# Modular_BO.net
KiCad netlist of a schematic drawn in Altium Designer
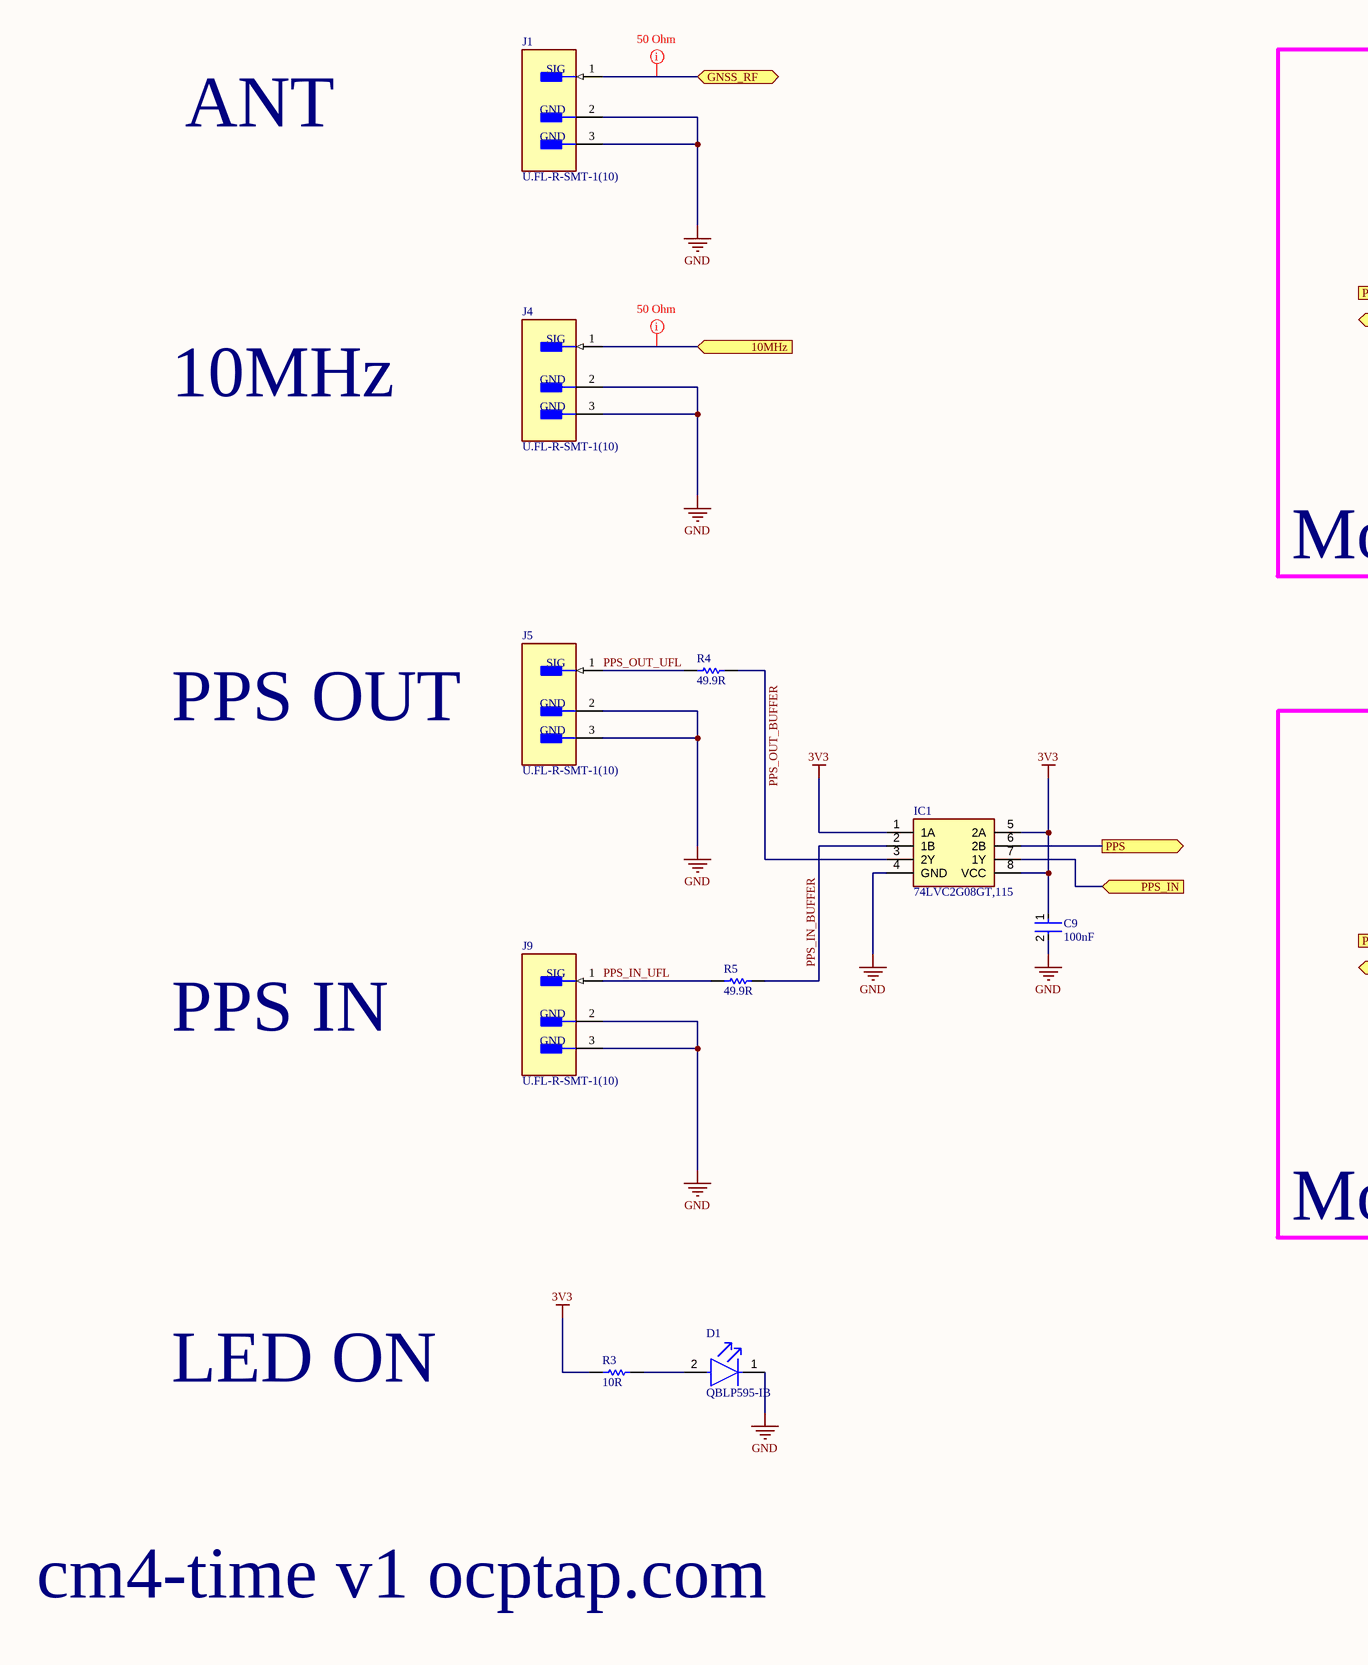
[diagram p0: Modular_BO.SchDoc, left]
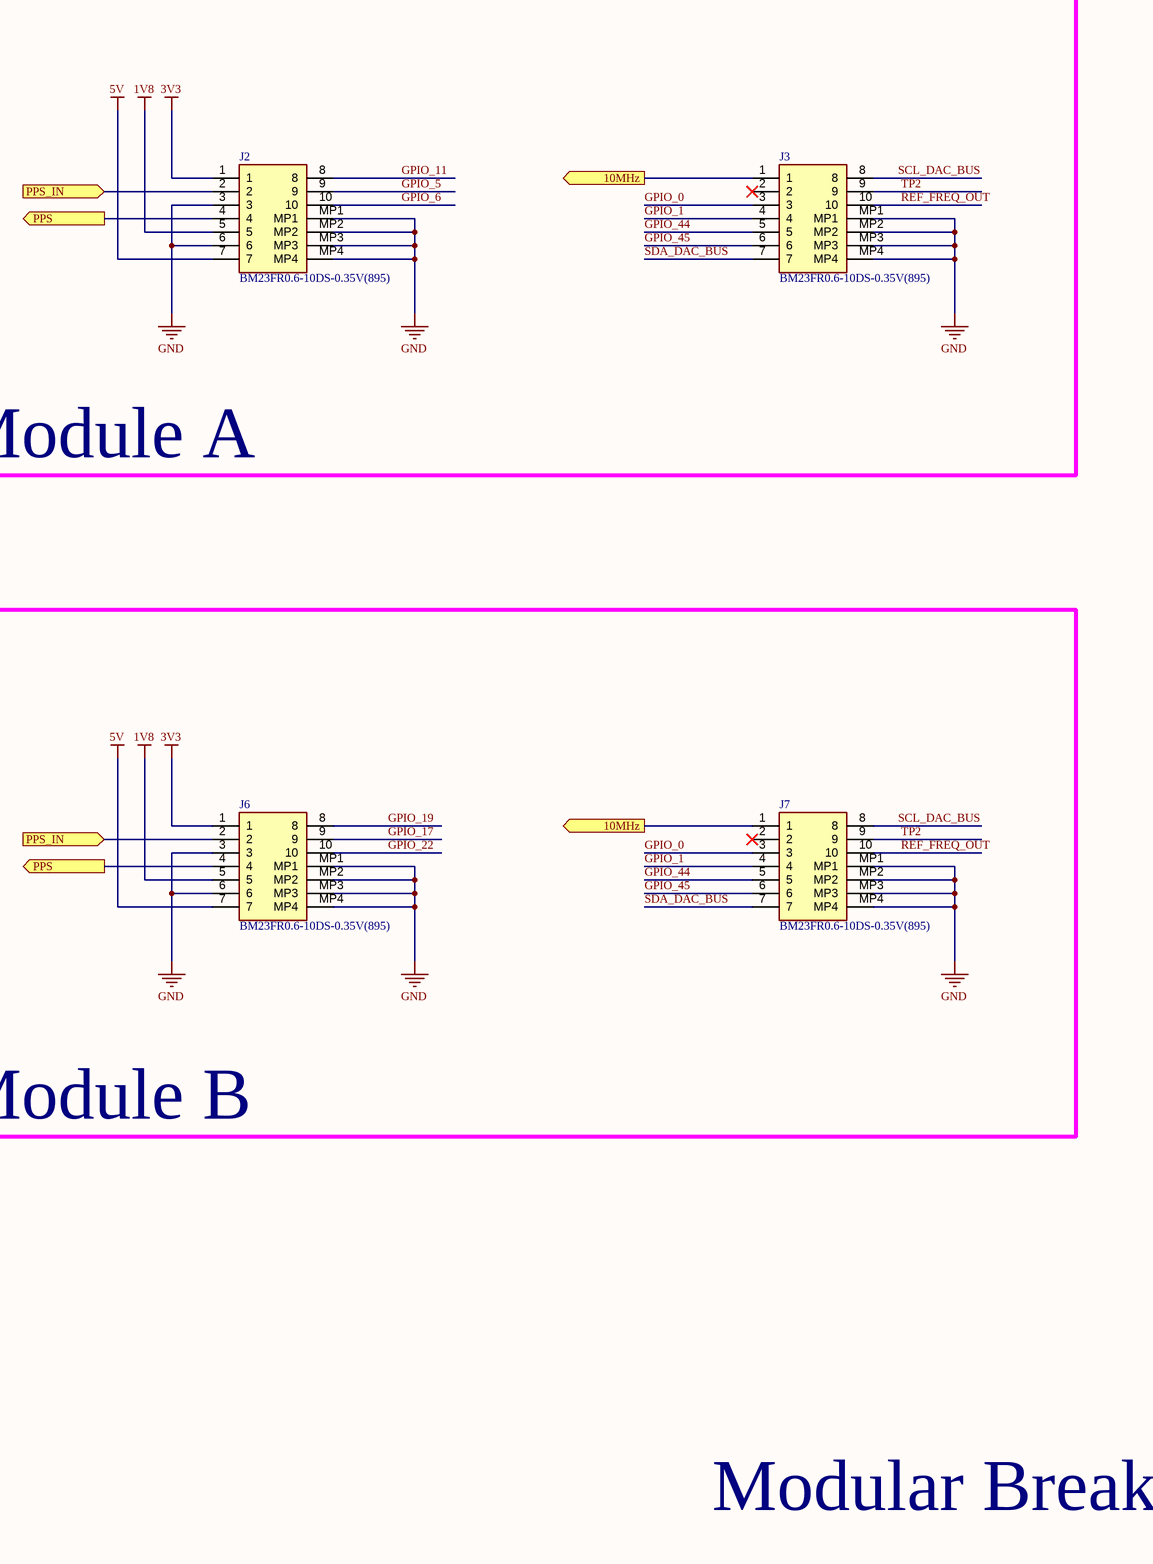
[diagram p1: Modular_BO.SchDoc, right]

(export (version "E")
  (design (tool "Eeschema 10.0.6"))
  (components
    (comp (ref "C9")
      (value "100nF")
      (footprint "FP-C0603C-CF-MFG")
      (description "CAP CER 0.1UF 50V 20% X7R 0603")
      (fields
        (field (name "MANUFACTURER PART NUMBER") "C0603C104M5RACTU")
        (field (name "MANUFACTURER") "KEMET")
      )
      (libsource (lib "Altium Content Vault") (part "b4654b650e69147ec39a6b967a45e02"))
    )
    (comp (ref "D1")
      (value "QBLP595-IB")
      (footprint "FP-QBLP595-IB-MFG")
      (description "LED BLUE CLEAR 0402 SMD")
      (libsource (lib "Altium Content Vault") (part "8706943c75ba83719d021d2fdc84c58"))
    )
    (comp (ref "IC1")
      (value "74LVC2G08GT,115")
      (footprint "SamacSys:74AVC9112GTX")
      (description "Integrated Circuit")
      (fields (field (name "MOUSER PART NUMBER") "771-LVC2G08GT115"))
      (libsource (lib "*") (part "74LVC2G08GT,115"))
    )
    (comp (ref "J1")
      (value "U.FL-R-SMT-1(10)")
      (footprint "FP-U_FL-R-SMT-1_10-MFG")
      (description "CONN U.FL RCPT STR 50 OHM SMD")
      (libsource (lib "Altium Content Vault") (part "7158abf7d987fa84906f6fb0d115710"))
    )
    (comp (ref "J2")
      (value "BM23FR0.6-10DS-0.35V(895)")
      (footprint "SamacSys:BM23FR0810DS035V895")
      (description "Connector")
      (fields
        (field (name "MANUFACTURER_PART_NUMBER") "BM23FR0.8-10DS-0.35V(895)")
        (field (name "MOUSER PART NUMBER") "798-3FR0810DS035V895")
      )
      (libsource (lib "*") (part "BM23FR0.8-10DS-0.35V_895_"))
    )
    (comp (ref "J3")
      (value "BM23FR0.6-10DS-0.35V(895)")
      (footprint "SamacSys:BM23FR0810DS035V895")
      (description "Connector")
      (fields
        (field (name "MANUFACTURER_PART_NUMBER") "BM23FR0.8-10DS-0.35V(895)")
        (field (name "MOUSER PART NUMBER") "798-3FR0810DS035V895")
      )
      (libsource (lib "*") (part "BM23FR0.8-10DS-0.35V_895_"))
    )
    (comp (ref "J4")
      (value "U.FL-R-SMT-1(10)")
      (footprint "FP-U_FL-R-SMT-1_10-MFG")
      (description "CONN U.FL RCPT STR 50 OHM SMD")
      (libsource (lib "Altium Content Vault") (part "7158abf7d987fa84906f6fb0d115710"))
    )
    (comp (ref "J5")
      (value "U.FL-R-SMT-1(10)")
      (footprint "FP-U_FL-R-SMT-1_10-MFG")
      (description "CONN U.FL RCPT STR 50 OHM SMD")
      (libsource (lib "Altium Content Vault") (part "7158abf7d987fa84906f6fb0d115710"))
    )
    (comp (ref "J6")
      (value "BM23FR0.6-10DS-0.35V(895)")
      (footprint "SamacSys:BM23FR0810DS035V895")
      (description "Connector")
      (fields
        (field (name "MANUFACTURER_PART_NUMBER") "BM23FR0.8-10DS-0.35V(895)")
        (field (name "MOUSER PART NUMBER") "798-3FR0810DS035V895")
      )
      (libsource (lib "*") (part "BM23FR0.8-10DS-0.35V_895_"))
    )
    (comp (ref "J7")
      (value "BM23FR0.6-10DS-0.35V(895)")
      (footprint "SamacSys:BM23FR0810DS035V895")
      (description "Connector")
      (fields
        (field (name "MANUFACTURER_PART_NUMBER") "BM23FR0.8-10DS-0.35V(895)")
        (field (name "MOUSER PART NUMBER") "798-3FR0810DS035V895")
      )
      (libsource (lib "*") (part "BM23FR0.8-10DS-0.35V_895_"))
    )
    (comp (ref "J9")
      (value "U.FL-R-SMT-1(10)")
      (footprint "FP-U_FL-R-SMT-1_10-MFG")
      (description "CONN U.FL RCPT STR 50 OHM SMD")
      (libsource (lib "Altium Content Vault") (part "7158abf7d987fa84906f6fb0d115710"))
    )
    (comp (ref "R3")
      (value "10R")
      (footprint "RESC1005X40X25NL05T10")
      (fields (field (name "PART NUMBER") "CRCW040210R0FKEDHP") (field (name "MANUFACTURER") "Vishay Dale"))
      (libsource (lib "Altium Content Vault") (part "RES"))
    )
    (comp (ref "R4")
      (value "49.9R")
      (footprint "RESC1608X55X25NL10T15")
      (libsource (lib "Altium Content Vault") (part "RES-2"))
    )
    (comp (ref "R5")
      (value "49.9R")
      (footprint "RESC1608X55X25NL10T15")
      (libsource (lib "Altium Content Vault") (part "RES-2"))
    )
  )
  (nets
    (net (code "1") (name "/10MHz") (class "Default")
      (node (ref "J3") (pin "1") (pinfunction "1_1") (pintype "passive"))
      (node (ref "J4") (pin "1") (pinfunction "SIG_1") (pintype "input"))
      (node (ref "J7") (pin "1") (pinfunction "1_1") (pintype "passive"))
    )
    (net (code "2") (name "/GNSS_RF") (class "Default")
      (node (ref "J1") (pin "1") (pinfunction "SIG_1") (pintype "input"))
    )
    (net (code "3") (name "/GPIO_0") (class "Default")
      (node (ref "J3") (pin "3") (pinfunction "3_3") (pintype "passive"))
      (node (ref "J7") (pin "3") (pinfunction "3_3") (pintype "passive"))
    )
    (net (code "4") (name "/GPIO_1") (class "Default")
      (node (ref "J3") (pin "4") (pinfunction "4_4") (pintype "passive"))
      (node (ref "J7") (pin "4") (pinfunction "4_4") (pintype "passive"))
    )
    (net (code "5") (name "/GPIO_5") (class "Default")
      (node (ref "J2") (pin "9") (pinfunction "9_9") (pintype "passive"))
    )
    (net (code "6") (name "/GPIO_6") (class "Default")
      (node (ref "J2") (pin "10") (pinfunction "10_10") (pintype "passive"))
    )
    (net (code "7") (name "/GPIO_11") (class "Default")
      (node (ref "J2") (pin "8") (pinfunction "8_8") (pintype "passive"))
    )
    (net (code "8") (name "/GPIO_17") (class "Default")
      (node (ref "J6") (pin "9") (pinfunction "9_9") (pintype "passive"))
    )
    (net (code "9") (name "/GPIO_19") (class "Default")
      (node (ref "J6") (pin "8") (pinfunction "8_8") (pintype "passive"))
    )
    (net (code "10") (name "/GPIO_22") (class "Default")
      (node (ref "J6") (pin "10") (pinfunction "10_10") (pintype "passive"))
    )
    (net (code "11") (name "/GPIO_44") (class "Default")
      (node (ref "J3") (pin "5") (pinfunction "5_5") (pintype "passive"))
      (node (ref "J7") (pin "5") (pinfunction "5_5") (pintype "passive"))
    )
    (net (code "12") (name "/GPIO_45") (class "Default")
      (node (ref "J3") (pin "6") (pinfunction "6_6") (pintype "passive"))
      (node (ref "J7") (pin "6") (pinfunction "6_6") (pintype "passive"))
    )
    (net (code "13") (name "/PPS") (class "Default")
      (node (ref "IC1") (pin "6") (pinfunction "2B_6") (pintype "passive"))
      (node (ref "J2") (pin "4") (pinfunction "4_4") (pintype "passive"))
      (node (ref "J6") (pin "4") (pinfunction "4_4") (pintype "passive"))
    )
    (net (code "14") (name "/PPS_IN") (class "Default")
      (node (ref "IC1") (pin "7") (pinfunction "1Y_7") (pintype "passive"))
      (node (ref "J2") (pin "2") (pinfunction "2_2") (pintype "passive"))
      (node (ref "J6") (pin "2") (pinfunction "2_2") (pintype "passive"))
    )
    (net (code "15") (name "/PPS_IN_BUFFER") (class "Default")
      (node (ref "IC1") (pin "2") (pinfunction "1B_2") (pintype "passive"))
      (node (ref "R5") (pin "2") (pinfunction "2_2") (pintype "passive"))
    )
    (net (code "16") (name "/PPS_IN_UFL") (class "Default")
      (node (ref "J9") (pin "1") (pinfunction "SIG_1") (pintype "input"))
      (node (ref "R5") (pin "1") (pinfunction "1_1") (pintype "passive"))
    )
    (net (code "17") (name "/PPS_OUT_BUFFER") (class "Default")
      (node (ref "IC1") (pin "3") (pinfunction "2Y_3") (pintype "passive"))
      (node (ref "R4") (pin "2") (pinfunction "2_2") (pintype "passive"))
    )
    (net (code "18") (name "/PPS_OUT_UFL") (class "Default")
      (node (ref "J5") (pin "1") (pinfunction "SIG_1") (pintype "input"))
      (node (ref "R4") (pin "1") (pinfunction "1_1") (pintype "passive"))
    )
    (net (code "19") (name "/REF_FREQ_OUT") (class "Default")
      (node (ref "J3") (pin "10") (pinfunction "10_10") (pintype "passive"))
      (node (ref "J7") (pin "10") (pinfunction "10_10") (pintype "passive"))
    )
    (net (code "20") (name "/SCL_DAC_BUS") (class "Default")
      (node (ref "J3") (pin "8") (pinfunction "8_8") (pintype "passive"))
      (node (ref "J7") (pin "8") (pinfunction "8_8") (pintype "passive"))
    )
    (net (code "21") (name "/SDA_DAC_BUS") (class "Default")
      (node (ref "J3") (pin "7") (pinfunction "7_7") (pintype "passive"))
      (node (ref "J7") (pin "7") (pinfunction "7_7") (pintype "passive"))
    )
    (net (code "22") (name "/TP2") (class "Default")
      (node (ref "J3") (pin "9") (pinfunction "9_9") (pintype "passive"))
      (node (ref "J7") (pin "9") (pinfunction "9_9") (pintype "passive"))
    )
    (net (code "23") (name "1V8") (class "Default")
      (node (ref "J2") (pin "5") (pinfunction "5_5") (pintype "passive"))
      (node (ref "J6") (pin "5") (pinfunction "5_5") (pintype "passive"))
    )
    (net (code "24") (name "3V3") (class "Default")
      (node (ref "C9") (pin "1") (pinfunction "1_1") (pintype "passive"))
      (node (ref "IC1") (pin "1") (pinfunction "1A_1") (pintype "passive"))
      (node (ref "IC1") (pin "5") (pinfunction "2A_5") (pintype "passive"))
      (node (ref "IC1") (pin "8") (pinfunction "VCC_8") (pintype "passive"))
      (node (ref "J2") (pin "1") (pinfunction "1_1") (pintype "passive"))
      (node (ref "J6") (pin "1") (pinfunction "1_1") (pintype "passive"))
      (node (ref "R3") (pin "1") (pinfunction "1_1") (pintype "passive"))
    )
    (net (code "25") (name "5V") (class "Default")
      (node (ref "J2") (pin "7") (pinfunction "7_7") (pintype "passive"))
      (node (ref "J6") (pin "7") (pinfunction "7_7") (pintype "passive"))
    )
    (net (code "26") (name "GND") (class "Default")
      (node (ref "C9") (pin "2") (pinfunction "2_2") (pintype "passive"))
      (node (ref "D1") (pin "1") (pinfunction "C_1") (pintype "passive"))
      (node (ref "IC1") (pin "4") (pinfunction "GND_4") (pintype "passive"))
      (node (ref "J1") (pin "2") (pinfunction "GND_2") (pintype "power_in"))
      (node (ref "J1") (pin "3") (pinfunction "GND_3") (pintype "power_in"))
      (node (ref "J2") (pin "3") (pinfunction "3_3") (pintype "passive"))
      (node (ref "J2") (pin "6") (pinfunction "6_6") (pintype "passive"))
      (node (ref "J2") (pin "MP1") (pinfunction "MP1_MP1") (pintype "passive"))
      (node (ref "J2") (pin "MP2") (pinfunction "MP2_MP2") (pintype "passive"))
      (node (ref "J2") (pin "MP3") (pinfunction "MP3_MP3") (pintype "passive"))
      (node (ref "J2") (pin "MP4") (pinfunction "MP4_MP4") (pintype "passive"))
      (node (ref "J3") (pin "MP1") (pinfunction "MP1_MP1") (pintype "passive"))
      (node (ref "J3") (pin "MP2") (pinfunction "MP2_MP2") (pintype "passive"))
      (node (ref "J3") (pin "MP3") (pinfunction "MP3_MP3") (pintype "passive"))
      (node (ref "J3") (pin "MP4") (pinfunction "MP4_MP4") (pintype "passive"))
      (node (ref "J4") (pin "2") (pinfunction "GND_2") (pintype "power_in"))
      (node (ref "J4") (pin "3") (pinfunction "GND_3") (pintype "power_in"))
      (node (ref "J5") (pin "2") (pinfunction "GND_2") (pintype "power_in"))
      (node (ref "J5") (pin "3") (pinfunction "GND_3") (pintype "power_in"))
      (node (ref "J6") (pin "3") (pinfunction "3_3") (pintype "passive"))
      (node (ref "J6") (pin "6") (pinfunction "6_6") (pintype "passive"))
      (node (ref "J6") (pin "MP1") (pinfunction "MP1_MP1") (pintype "passive"))
      (node (ref "J6") (pin "MP2") (pinfunction "MP2_MP2") (pintype "passive"))
      (node (ref "J6") (pin "MP3") (pinfunction "MP3_MP3") (pintype "passive"))
      (node (ref "J6") (pin "MP4") (pinfunction "MP4_MP4") (pintype "passive"))
      (node (ref "J7") (pin "MP1") (pinfunction "MP1_MP1") (pintype "passive"))
      (node (ref "J7") (pin "MP2") (pinfunction "MP2_MP2") (pintype "passive"))
      (node (ref "J7") (pin "MP3") (pinfunction "MP3_MP3") (pintype "passive"))
      (node (ref "J7") (pin "MP4") (pinfunction "MP4_MP4") (pintype "passive"))
      (node (ref "J9") (pin "2") (pinfunction "GND_2") (pintype "power_in"))
      (node (ref "J9") (pin "3") (pinfunction "GND_3") (pintype "power_in"))
    )
    (net (code "27") (name "Net-(D1-A)") (class "Default")
      (node (ref "D1") (pin "2") (pinfunction "A_2") (pintype "passive"))
      (node (ref "R3") (pin "2") (pinfunction "2_2") (pintype "passive"))
    )
    (net (code "28") (name "unconnected-(J3-Pad2)") (class "Default")
      (node (ref "J3") (pin "2") (pinfunction "2_2") (pintype "passive+no_connect"))
    )
    (net (code "29") (name "unconnected-(J7-Pad2)") (class "Default")
      (node (ref "J7") (pin "2") (pinfunction "2_2") (pintype "passive+no_connect"))
    )
  )
)
